# Lighthouse_Sensor.net
KiCad netlist of a schematic drawn in EAGLE
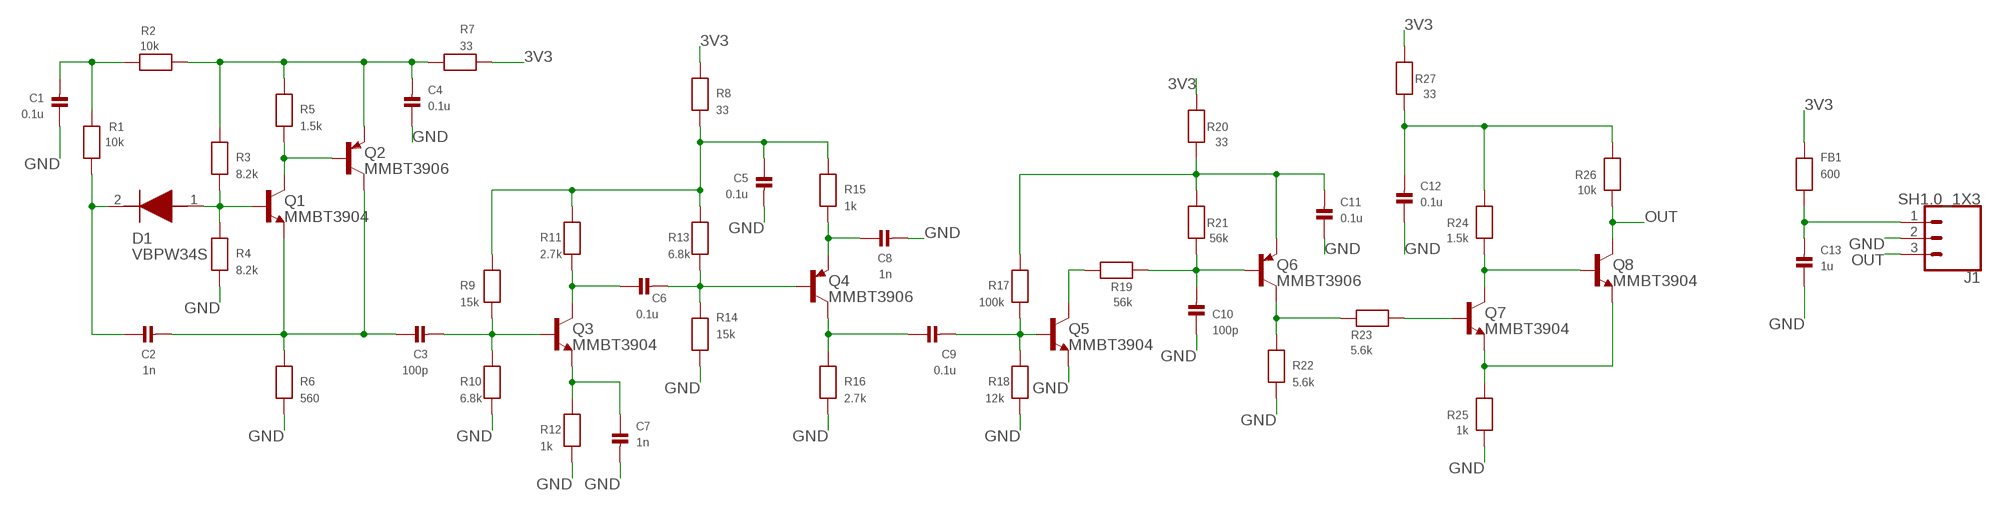
[diagram p0: schematic, sheet 1]

(export (version "E")
  (design (tool "Eeschema 10.0.6"))
  (components
    (comp (ref "C1")
      (value "0.1u")
      (footprint "eagle-import:C0603")
      (libsource (lib "eagle-import") (part "CAP_CERAMIC_C0603"))
    )
    (comp (ref "C2")
      (value "1n")
      (footprint "eagle-import:C0603")
      (libsource (lib "eagle-import") (part "CAP_CERAMIC_C0603"))
    )
    (comp (ref "C3")
      (value "100p")
      (footprint "eagle-import:C0603")
      (libsource (lib "eagle-import") (part "CAP_CERAMIC_C0603"))
    )
    (comp (ref "C4")
      (value "0.1u")
      (footprint "eagle-import:C0603")
      (libsource (lib "eagle-import") (part "CAP_CERAMIC_C0603"))
    )
    (comp (ref "C5")
      (value "0.1u")
      (footprint "eagle-import:C0603")
      (libsource (lib "eagle-import") (part "CAP_CERAMIC_C0603"))
    )
    (comp (ref "C6")
      (value "0.1u")
      (footprint "eagle-import:C0603")
      (libsource (lib "eagle-import") (part "CAP_CERAMIC_C0603"))
    )
    (comp (ref "C7")
      (value "1n")
      (footprint "eagle-import:C0603")
      (libsource (lib "eagle-import") (part "CAP_CERAMIC_C0603"))
    )
    (comp (ref "C8")
      (value "1n")
      (footprint "eagle-import:C0603")
      (libsource (lib "eagle-import") (part "CAP_CERAMIC_C0603"))
    )
    (comp (ref "C9")
      (value "0.1u")
      (footprint "eagle-import:C0603")
      (libsource (lib "eagle-import") (part "CAP_CERAMIC_C0603"))
    )
    (comp (ref "C10")
      (value "100p")
      (footprint "eagle-import:C0603")
      (libsource (lib "eagle-import") (part "CAP_CERAMIC_C0603"))
    )
    (comp (ref "C11")
      (value "0.1u")
      (footprint "eagle-import:C0603")
      (libsource (lib "eagle-import") (part "CAP_CERAMIC_C0603"))
    )
    (comp (ref "C12")
      (value "0.1u")
      (footprint "eagle-import:C0603")
      (libsource (lib "eagle-import") (part "CAP_CERAMIC_C0603"))
    )
    (comp (ref "C13")
      (value "1u")
      (footprint "eagle-import:C0603")
      (libsource (lib "eagle-import") (part "CAP_CERAMIC_C0603"))
    )
    (comp (ref "D1")
      (value "VBPW34S")
      (footprint "eagle-import:VBPW34S")
      (fields (field (name "MOUSER_PART_NUMBER") "782-VBPW34S"))
      (libsource (lib "eagle-import") (part "VBPW34S"))
    )
    (comp (ref "FB1")
      (value "600")
      (footprint "eagle-import:R0603")
      (libsource (lib "eagle-import") (part "RESISTOR_R0603"))
    )
    (comp (ref "J1")
      (value "SH1.0_1X3")
      (footprint "eagle-import:1X03_1MM_RA")
      (fields (field (name "SPICEPREFIX") "J"))
      (libsource (lib "eagle-import") (part "SH1.0_1X3"))
    )
    (comp (ref "Q1")
      (value "MMBT3904")
      (footprint "eagle-import:SOT23-BEC")
      (libsource (lib "eagle-import") (part "BC849SMD"))
    )
    (comp (ref "Q2")
      (value "MMBT3906")
      (footprint "eagle-import:SOT23-BEC")
      (libsource (lib "eagle-import") (part "MMBT3906SMDLT1"))
    )
    (comp (ref "Q3")
      (value "MMBT3904")
      (footprint "eagle-import:SOT23-BEC")
      (libsource (lib "eagle-import") (part "BC849SMD"))
    )
    (comp (ref "Q4")
      (value "MMBT3906")
      (footprint "eagle-import:SOT23-BEC")
      (libsource (lib "eagle-import") (part "MMBT3906SMDLT1"))
    )
    (comp (ref "Q5")
      (value "MMBT3904")
      (footprint "eagle-import:SOT23-BEC")
      (libsource (lib "eagle-import") (part "BC849SMD"))
    )
    (comp (ref "Q6")
      (value "MMBT3906")
      (footprint "eagle-import:SOT23-BEC")
      (libsource (lib "eagle-import") (part "MMBT3906SMDLT1"))
    )
    (comp (ref "Q7")
      (value "MMBT3904")
      (footprint "eagle-import:SOT23-BEC")
      (libsource (lib "eagle-import") (part "BC849SMD"))
    )
    (comp (ref "Q8")
      (value "MMBT3904")
      (footprint "eagle-import:SOT23-BEC")
      (libsource (lib "eagle-import") (part "BC849SMD"))
    )
    (comp (ref "R1")
      (value "10k")
      (footprint "eagle-import:R0603")
      (libsource (lib "eagle-import") (part "RESISTOR_R0603"))
    )
    (comp (ref "R2")
      (value "10k")
      (footprint "eagle-import:R0603")
      (libsource (lib "eagle-import") (part "RESISTOR_R0603"))
    )
    (comp (ref "R3")
      (value "8.2k")
      (footprint "eagle-import:R0603")
      (libsource (lib "eagle-import") (part "RESISTOR_R0603"))
    )
    (comp (ref "R4")
      (value "8.2k")
      (footprint "eagle-import:R0603")
      (libsource (lib "eagle-import") (part "RESISTOR_R0603"))
    )
    (comp (ref "R5")
      (value "1.5k")
      (footprint "eagle-import:R0603")
      (libsource (lib "eagle-import") (part "RESISTOR_R0603"))
    )
    (comp (ref "R6")
      (value "560")
      (footprint "eagle-import:R0603")
      (libsource (lib "eagle-import") (part "RESISTOR_R0603"))
    )
    (comp (ref "R7")
      (value "33")
      (footprint "eagle-import:R0603")
      (libsource (lib "eagle-import") (part "RESISTOR_R0603"))
    )
    (comp (ref "R8")
      (value "33")
      (footprint "eagle-import:R0603")
      (libsource (lib "eagle-import") (part "RESISTOR_R0603"))
    )
    (comp (ref "R9")
      (value "15k")
      (footprint "eagle-import:R0603")
      (libsource (lib "eagle-import") (part "RESISTOR_R0603"))
    )
    (comp (ref "R10")
      (value "6.8k")
      (footprint "eagle-import:R0603")
      (libsource (lib "eagle-import") (part "RESISTOR_R0603"))
    )
    (comp (ref "R11")
      (value "2.7k")
      (footprint "eagle-import:R0603")
      (libsource (lib "eagle-import") (part "RESISTOR_R0603"))
    )
    (comp (ref "R12")
      (value "1k")
      (footprint "eagle-import:R0603")
      (libsource (lib "eagle-import") (part "RESISTOR_R0603"))
    )
    (comp (ref "R13")
      (value "6.8k")
      (footprint "eagle-import:R0603")
      (libsource (lib "eagle-import") (part "RESISTOR_R0603"))
    )
    (comp (ref "R14")
      (value "15k")
      (footprint "eagle-import:R0603")
      (libsource (lib "eagle-import") (part "RESISTOR_R0603"))
    )
    (comp (ref "R15")
      (value "1k")
      (footprint "eagle-import:R0603")
      (libsource (lib "eagle-import") (part "RESISTOR_R0603"))
    )
    (comp (ref "R16")
      (value "2.7k")
      (footprint "eagle-import:R0603")
      (libsource (lib "eagle-import") (part "RESISTOR_R0603"))
    )
    (comp (ref "R17")
      (value "100k")
      (footprint "eagle-import:R0603")
      (libsource (lib "eagle-import") (part "RESISTOR_R0603"))
    )
    (comp (ref "R18")
      (value "12k")
      (footprint "eagle-import:R0603")
      (libsource (lib "eagle-import") (part "RESISTOR_R0603"))
    )
    (comp (ref "R19")
      (value "56k")
      (footprint "eagle-import:R0603")
      (libsource (lib "eagle-import") (part "RESISTOR_R0603"))
    )
    (comp (ref "R20")
      (value "33")
      (footprint "eagle-import:R0603")
      (libsource (lib "eagle-import") (part "RESISTOR_R0603"))
    )
    (comp (ref "R21")
      (value "56k")
      (footprint "eagle-import:R0603")
      (libsource (lib "eagle-import") (part "RESISTOR_R0603"))
    )
    (comp (ref "R22")
      (value "5.6k")
      (footprint "eagle-import:R0603")
      (libsource (lib "eagle-import") (part "RESISTOR_R0603"))
    )
    (comp (ref "R23")
      (value "5.6k")
      (footprint "eagle-import:R0603")
      (libsource (lib "eagle-import") (part "RESISTOR_R0603"))
    )
    (comp (ref "R24")
      (value "1.5k")
      (footprint "eagle-import:R0603")
      (libsource (lib "eagle-import") (part "RESISTOR_R0603"))
    )
    (comp (ref "R25")
      (value "1k")
      (footprint "eagle-import:R0603")
      (libsource (lib "eagle-import") (part "RESISTOR_R0603"))
    )
    (comp (ref "R26")
      (value "10k")
      (footprint "eagle-import:R0603")
      (libsource (lib "eagle-import") (part "RESISTOR_R0603"))
    )
    (comp (ref "R27")
      (value "33")
      (footprint "eagle-import:R0603")
      (libsource (lib "eagle-import") (part "RESISTOR_R0603"))
    )
  )
  (nets
    (net (code "1") (name "/3V3") (class "Default")
      (node (ref "FB1") (pin "2") (pinfunction "2_2") (pintype "passive"))
      (node (ref "R20") (pin "2") (pinfunction "2_2") (pintype "passive"))
      (node (ref "R27") (pin "2") (pinfunction "2_2") (pintype "passive"))
      (node (ref "R7") (pin "2") (pinfunction "2_2") (pintype "passive"))
      (node (ref "R8") (pin "1") (pinfunction "1_1") (pintype "passive"))
    )
    (net (code "2") (name "/GND") (class "Default")
      (node (ref "C1") (pin "1") (pinfunction "P$1_1") (pintype "passive"))
      (node (ref "C10") (pin "1") (pinfunction "P$1_1") (pintype "passive"))
      (node (ref "C11") (pin "1") (pinfunction "P$1_1") (pintype "passive"))
      (node (ref "C12") (pin "1") (pinfunction "P$1_1") (pintype "passive"))
      (node (ref "C13") (pin "1") (pinfunction "P$1_1") (pintype "passive"))
      (node (ref "C4") (pin "1") (pinfunction "P$1_1") (pintype "passive"))
      (node (ref "C5") (pin "2") (pinfunction "P$2_2") (pintype "passive"))
      (node (ref "C7") (pin "2") (pinfunction "P$2_2") (pintype "passive"))
      (node (ref "C8") (pin "2") (pinfunction "P$2_2") (pintype "passive"))
      (node (ref "J1") (pin "2") (pinfunction "2_2") (pintype "power_in"))
      (node (ref "Q5") (pin "E") (pinfunction "E_E") (pintype "passive"))
      (node (ref "R10") (pin "2") (pinfunction "2_2") (pintype "passive"))
      (node (ref "R12") (pin "2") (pinfunction "2_2") (pintype "passive"))
      (node (ref "R14") (pin "2") (pinfunction "2_2") (pintype "passive"))
      (node (ref "R16") (pin "2") (pinfunction "2_2") (pintype "passive"))
      (node (ref "R18") (pin "2") (pinfunction "2_2") (pintype "passive"))
      (node (ref "R22") (pin "1") (pinfunction "1_1") (pintype "passive"))
      (node (ref "R25") (pin "2") (pinfunction "2_2") (pintype "passive"))
      (node (ref "R4") (pin "2") (pinfunction "2_2") (pintype "passive"))
      (node (ref "R6") (pin "2") (pinfunction "2_2") (pintype "passive"))
    )
    (net (code "3") (name "/OUT") (class "Default")
      (node (ref "J1") (pin "3") (pinfunction "3_3") (pintype "passive"))
      (node (ref "Q8") (pin "C") (pinfunction "C_C") (pintype "passive"))
      (node (ref "R26") (pin "2") (pinfunction "2_2") (pintype "passive"))
    )
    (net (code "4") (name "Net-(C1-P$2)") (class "Default")
      (node (ref "C1") (pin "2") (pinfunction "P$2_2") (pintype "passive"))
      (node (ref "R1") (pin "2") (pinfunction "2_2") (pintype "passive"))
      (node (ref "R2") (pin "2") (pinfunction "2_2") (pintype "passive"))
    )
    (net (code "5") (name "Net-(C2-P$1)") (class "Default")
      (node (ref "C2") (pin "1") (pinfunction "P$1_1") (pintype "passive"))
      (node (ref "D1") (pin "2") (pinfunction "K_2") (pintype "bidirectional"))
      (node (ref "R1") (pin "1") (pinfunction "1_1") (pintype "passive"))
    )
    (net (code "6") (name "Net-(C2-P$2)") (class "Default")
      (node (ref "C2") (pin "2") (pinfunction "P$2_2") (pintype "passive"))
      (node (ref "C3") (pin "1") (pinfunction "P$1_1") (pintype "passive"))
      (node (ref "Q1") (pin "E") (pinfunction "E_E") (pintype "passive"))
      (node (ref "Q2") (pin "C") (pinfunction "C_C") (pintype "passive"))
      (node (ref "R6") (pin "1") (pinfunction "1_1") (pintype "passive"))
    )
    (net (code "7") (name "Net-(C3-P$2)") (class "Default")
      (node (ref "C3") (pin "2") (pinfunction "P$2_2") (pintype "passive"))
      (node (ref "Q3") (pin "B") (pinfunction "B_B") (pintype "passive"))
      (node (ref "R10") (pin "1") (pinfunction "1_1") (pintype "passive"))
      (node (ref "R9") (pin "2") (pinfunction "2_2") (pintype "passive"))
    )
    (net (code "8") (name "Net-(C4-P$2)") (class "Default")
      (node (ref "C4") (pin "2") (pinfunction "P$2_2") (pintype "passive"))
      (node (ref "Q2") (pin "E") (pinfunction "E_E") (pintype "passive"))
      (node (ref "R2") (pin "1") (pinfunction "1_1") (pintype "passive"))
      (node (ref "R3") (pin "1") (pinfunction "1_1") (pintype "passive"))
      (node (ref "R5") (pin "1") (pinfunction "1_1") (pintype "passive"))
      (node (ref "R7") (pin "1") (pinfunction "1_1") (pintype "passive"))
    )
    (net (code "9") (name "Net-(C5-P$1)") (class "Default")
      (node (ref "C5") (pin "1") (pinfunction "P$1_1") (pintype "passive"))
      (node (ref "R11") (pin "1") (pinfunction "1_1") (pintype "passive"))
      (node (ref "R13") (pin "1") (pinfunction "1_1") (pintype "passive"))
      (node (ref "R15") (pin "1") (pinfunction "1_1") (pintype "passive"))
      (node (ref "R8") (pin "2") (pinfunction "2_2") (pintype "passive"))
      (node (ref "R9") (pin "1") (pinfunction "1_1") (pintype "passive"))
    )
    (net (code "10") (name "Net-(C6-P$1)") (class "Default")
      (node (ref "C6") (pin "1") (pinfunction "P$1_1") (pintype "passive"))
      (node (ref "Q3") (pin "C") (pinfunction "C_C") (pintype "passive"))
      (node (ref "R11") (pin "2") (pinfunction "2_2") (pintype "passive"))
    )
    (net (code "11") (name "Net-(C6-P$2)") (class "Default")
      (node (ref "C6") (pin "2") (pinfunction "P$2_2") (pintype "passive"))
      (node (ref "Q4") (pin "B") (pinfunction "B_B") (pintype "passive"))
      (node (ref "R13") (pin "2") (pinfunction "2_2") (pintype "passive"))
      (node (ref "R14") (pin "1") (pinfunction "1_1") (pintype "passive"))
    )
    (net (code "12") (name "Net-(C7-P$1)") (class "Default")
      (node (ref "C7") (pin "1") (pinfunction "P$1_1") (pintype "passive"))
      (node (ref "Q3") (pin "E") (pinfunction "E_E") (pintype "passive"))
      (node (ref "R12") (pin "1") (pinfunction "1_1") (pintype "passive"))
    )
    (net (code "13") (name "Net-(C8-P$1)") (class "Default")
      (node (ref "C8") (pin "1") (pinfunction "P$1_1") (pintype "passive"))
      (node (ref "Q4") (pin "E") (pinfunction "E_E") (pintype "passive"))
      (node (ref "R15") (pin "2") (pinfunction "2_2") (pintype "passive"))
    )
    (net (code "14") (name "Net-(C9-P$1)") (class "Default")
      (node (ref "C9") (pin "1") (pinfunction "P$1_1") (pintype "passive"))
      (node (ref "Q4") (pin "C") (pinfunction "C_C") (pintype "passive"))
      (node (ref "R16") (pin "1") (pinfunction "1_1") (pintype "passive"))
    )
    (net (code "15") (name "Net-(C9-P$2)") (class "Default")
      (node (ref "C9") (pin "2") (pinfunction "P$2_2") (pintype "passive"))
      (node (ref "Q5") (pin "B") (pinfunction "B_B") (pintype "passive"))
      (node (ref "R17") (pin "2") (pinfunction "2_2") (pintype "passive"))
      (node (ref "R18") (pin "1") (pinfunction "1_1") (pintype "passive"))
    )
    (net (code "16") (name "Net-(C10-P$2)") (class "Default")
      (node (ref "C10") (pin "2") (pinfunction "P$2_2") (pintype "passive"))
      (node (ref "Q6") (pin "B") (pinfunction "B_B") (pintype "passive"))
      (node (ref "R19") (pin "2") (pinfunction "2_2") (pintype "passive"))
      (node (ref "R21") (pin "1") (pinfunction "1_1") (pintype "passive"))
    )
    (net (code "17") (name "Net-(C11-P$2)") (class "Default")
      (node (ref "C11") (pin "2") (pinfunction "P$2_2") (pintype "passive"))
      (node (ref "Q6") (pin "E") (pinfunction "E_E") (pintype "passive"))
      (node (ref "R17") (pin "1") (pinfunction "1_1") (pintype "passive"))
      (node (ref "R20") (pin "1") (pinfunction "1_1") (pintype "passive"))
      (node (ref "R21") (pin "2") (pinfunction "2_2") (pintype "passive"))
    )
    (net (code "18") (name "Net-(C12-P$2)") (class "Default")
      (node (ref "C12") (pin "2") (pinfunction "P$2_2") (pintype "passive"))
      (node (ref "R24") (pin "1") (pinfunction "1_1") (pintype "passive"))
      (node (ref "R26") (pin "1") (pinfunction "1_1") (pintype "passive"))
      (node (ref "R27") (pin "1") (pinfunction "1_1") (pintype "passive"))
    )
    (net (code "19") (name "Net-(C13-P$2)") (class "Default")
      (node (ref "C13") (pin "2") (pinfunction "P$2_2") (pintype "passive"))
      (node (ref "FB1") (pin "1") (pinfunction "1_1") (pintype "passive"))
      (node (ref "J1") (pin "1") (pinfunction "1_1") (pintype "power_in"))
    )
    (net (code "20") (name "Net-(D1-A)") (class "Default")
      (node (ref "D1") (pin "1") (pinfunction "A_1") (pintype "bidirectional"))
      (node (ref "Q1") (pin "B") (pinfunction "B_B") (pintype "passive"))
      (node (ref "R3") (pin "2") (pinfunction "2_2") (pintype "passive"))
      (node (ref "R4") (pin "1") (pinfunction "1_1") (pintype "passive"))
    )
    (net (code "21") (name "Net-(Q1-PadC)") (class "Default")
      (node (ref "Q1") (pin "C") (pinfunction "C_C") (pintype "passive"))
      (node (ref "Q2") (pin "B") (pinfunction "B_B") (pintype "passive"))
      (node (ref "R5") (pin "2") (pinfunction "2_2") (pintype "passive"))
    )
    (net (code "22") (name "Net-(Q5-PadC)") (class "Default")
      (node (ref "Q5") (pin "C") (pinfunction "C_C") (pintype "passive"))
      (node (ref "R19") (pin "1") (pinfunction "1_1") (pintype "passive"))
    )
    (net (code "23") (name "Net-(Q6-PadC)") (class "Default")
      (node (ref "Q6") (pin "C") (pinfunction "C_C") (pintype "passive"))
      (node (ref "R22") (pin "2") (pinfunction "2_2") (pintype "passive"))
      (node (ref "R23") (pin "2") (pinfunction "2_2") (pintype "passive"))
    )
    (net (code "24") (name "Net-(Q7-PadB)") (class "Default")
      (node (ref "Q7") (pin "B") (pinfunction "B_B") (pintype "passive"))
      (node (ref "R23") (pin "1") (pinfunction "1_1") (pintype "passive"))
    )
    (net (code "25") (name "Net-(Q7-PadC)") (class "Default")
      (node (ref "Q7") (pin "C") (pinfunction "C_C") (pintype "passive"))
      (node (ref "Q8") (pin "B") (pinfunction "B_B") (pintype "passive"))
      (node (ref "R24") (pin "2") (pinfunction "2_2") (pintype "passive"))
    )
    (net (code "26") (name "Net-(Q7-PadE)") (class "Default")
      (node (ref "Q7") (pin "E") (pinfunction "E_E") (pintype "passive"))
      (node (ref "Q8") (pin "E") (pinfunction "E_E") (pintype "passive"))
      (node (ref "R25") (pin "1") (pinfunction "1_1") (pintype "passive"))
    )
  )
)
